# motion_sensor.net
KiCad netlist of a schematic drawn in EAGLE
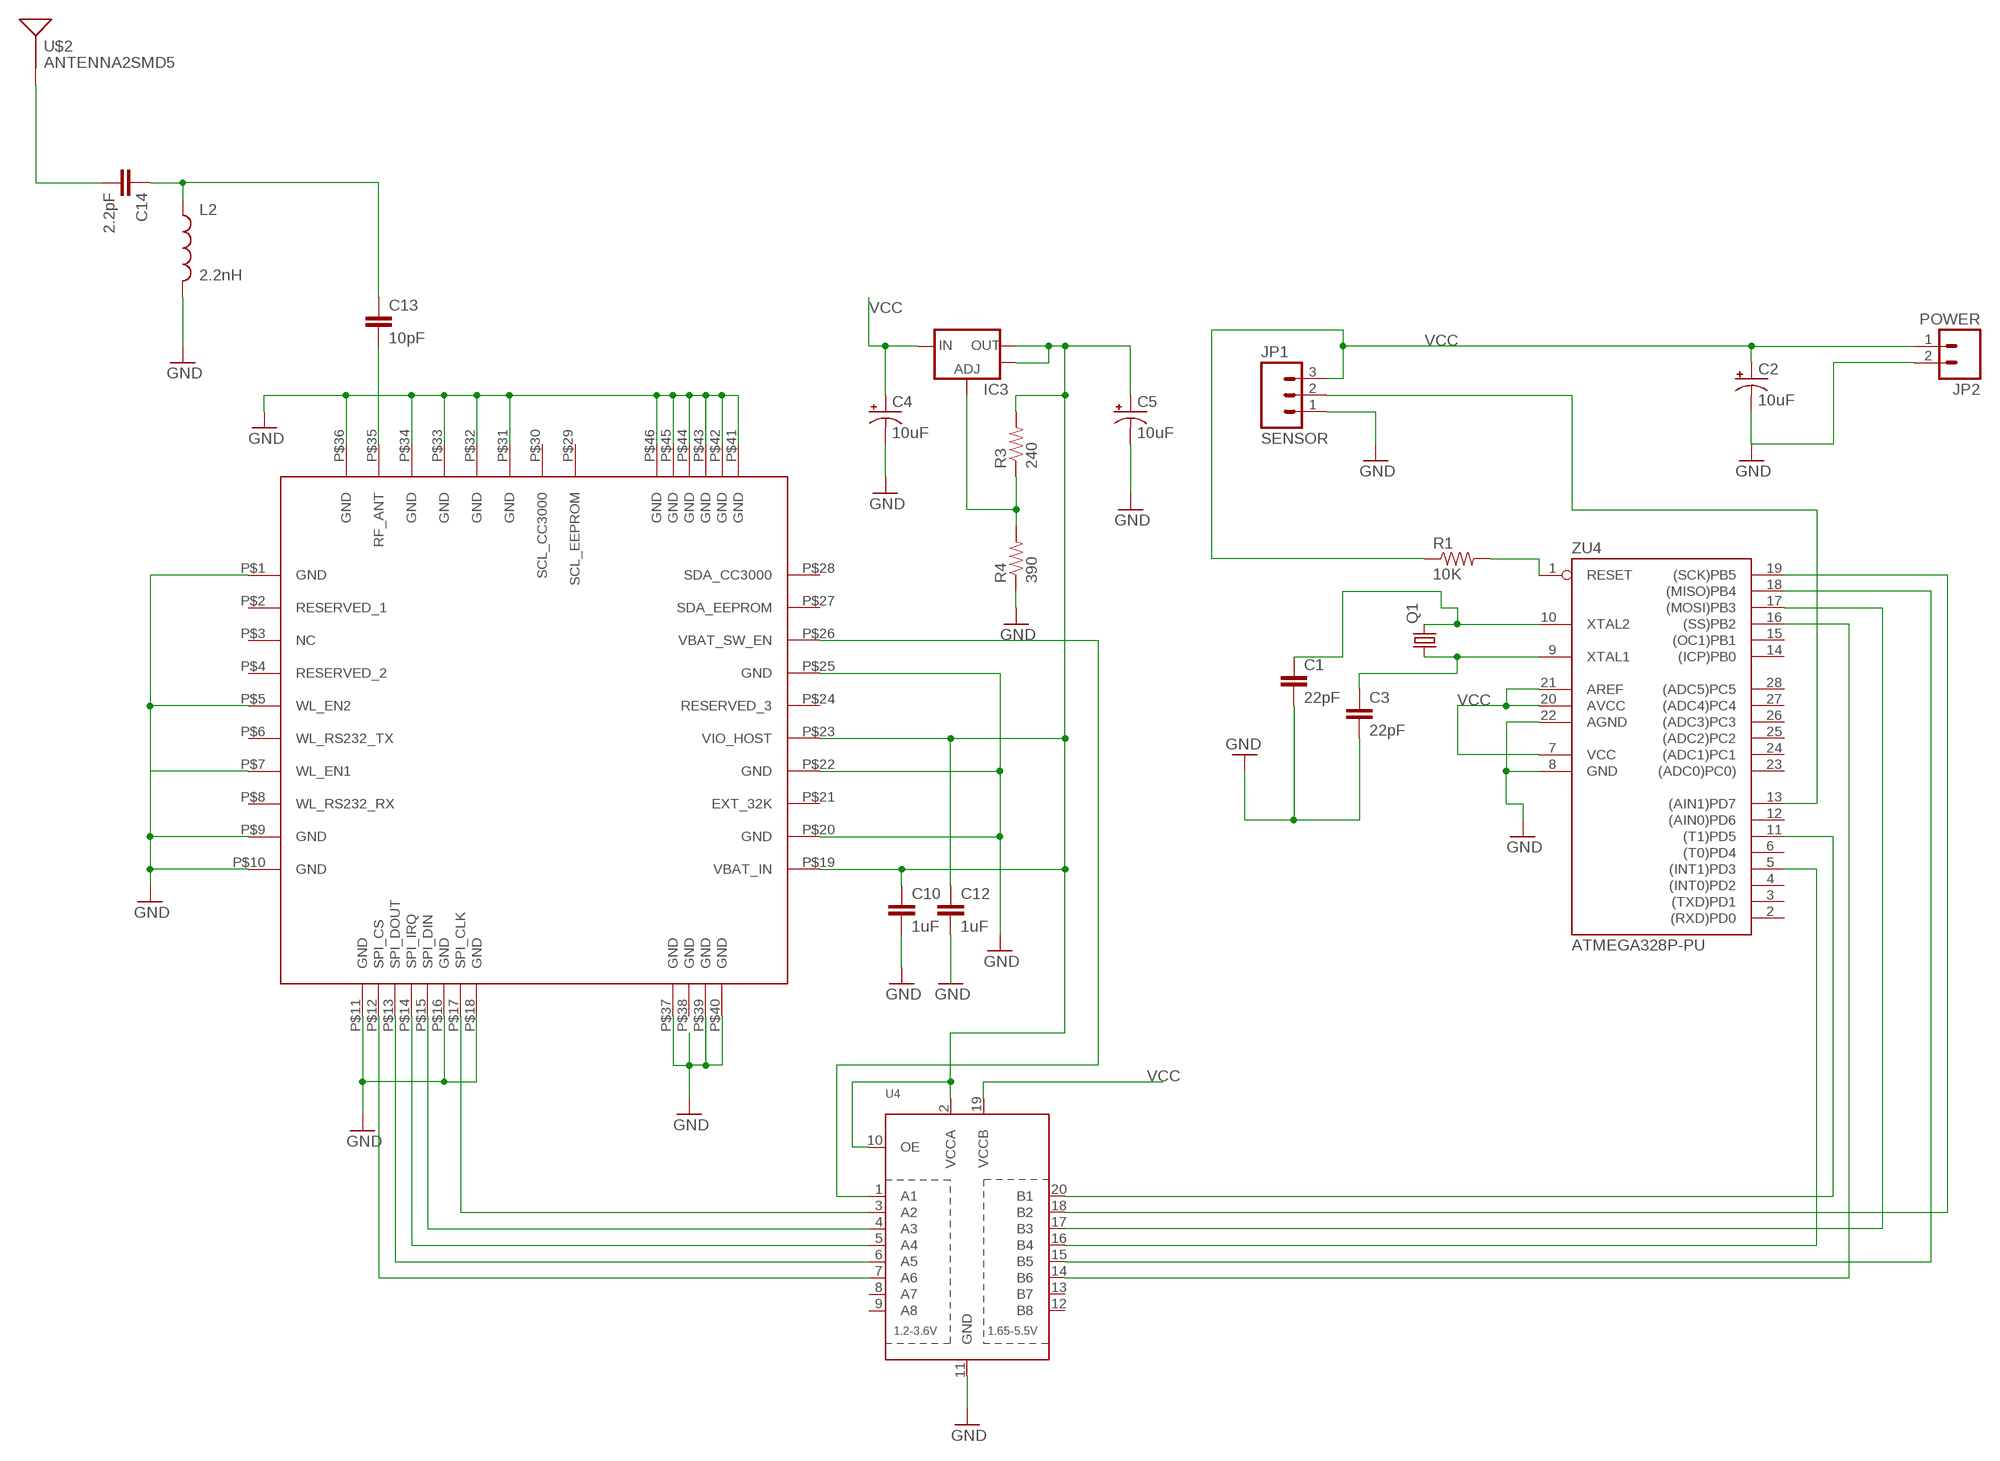
[diagram p0: schematic, sheet 1]

(export (version "E")
  (design (tool "Eeschema 10.0.6"))
  (components
    (comp (ref "C1")
      (value "22pF")
      (footprint "eagle-import:0805")
      (libsource (lib "eagle-import") (part "SparkFun-Passives_CAP0805"))
    )
    (comp (ref "C2")
      (value "10uF")
      (footprint "eagle-import:EIA3216")
      (libsource (lib "eagle-import") (part "CAP_POL1206"))
    )
    (comp (ref "C3")
      (value "22pF")
      (footprint "eagle-import:0805")
      (libsource (lib "eagle-import") (part "SparkFun-Passives_CAP0805"))
    )
    (comp (ref "C4")
      (value "10uF")
      (footprint "eagle-import:EIA3528")
      (libsource (lib "eagle-import") (part "CAP_POL3528"))
    )
    (comp (ref "C5")
      (value "10uF")
      (footprint "eagle-import:EIA3528")
      (libsource (lib "eagle-import") (part "CAP_POL3528"))
    )
    (comp (ref "C10")
      (value "1uF")
      (footprint "eagle-import:1206")
      (libsource (lib "eagle-import") (part "CAP1206"))
    )
    (comp (ref "C12")
      (value "1uF")
      (footprint "eagle-import:1206")
      (libsource (lib "eagle-import") (part "CAP1206"))
    )
    (comp (ref "C13")
      (value "10pF")
      (footprint "eagle-import:0805")
      (libsource (lib "eagle-import") (part "CAP0805"))
    )
    (comp (ref "C14")
      (value "2.2pF")
      (footprint "eagle-import:0805")
      (libsource (lib "eagle-import") (part "CAP0805"))
    )
    (comp (ref "IC3")
      (value "V_REG_LM1117SOT223")
      (footprint "eagle-import:SOT223")
      (libsource (lib "eagle-import") (part "V_REG_LM1117SOT223"))
    )
    (comp (ref "JP1")
      (value "SENSOR")
      (footprint "eagle-import:1X03")
      (libsource (lib "eagle-import") (part "M03PTH"))
    )
    (comp (ref "JP2")
      (value "POWER")
      (footprint "eagle-import:1X02")
      (libsource (lib "eagle-import") (part "M02PTH"))
    )
    (comp (ref "L2")
      (value "2.2nH")
      (footprint "eagle-import:0805")
      (libsource (lib "eagle-import") (part "INDUCTOR0805"))
    )
    (comp (ref "Q1")
      (value "CRYSTALHC49U-V")
      (footprint "eagle-import:HC49U-V")
      (libsource (lib "eagle-import") (part "CRYSTALHC49U-V"))
    )
    (comp (ref "R1")
      (value "10K")
      (footprint "eagle-import:0805")
      (libsource (lib "eagle-import") (part "RESISTOR0805-RES"))
    )
    (comp (ref "R3")
      (value "240")
      (footprint "eagle-import:0805")
      (libsource (lib "eagle-import") (part "SparkFun-Resistors_RESISTOR0805-RES"))
    )
    (comp (ref "R4")
      (value "390")
      (footprint "eagle-import:0805")
      (libsource (lib "eagle-import") (part "SparkFun-Resistors_RESISTOR0805-RES"))
    )
    (comp (ref "U$1")
      (value "CC3000")
      (footprint "eagle-import:CC3000")
      (fields (field (name "AUTHOR") "Matt Bigarani"))
      (libsource (lib "eagle-import") (part "CC3000"))
    )
    (comp (ref "U$2")
      (value "ANTENNA2SMD5")
      (footprint "eagle-import:ANTENNA-CHIP5")
      (libsource (lib "eagle-import") (part "ANTENNA2SMD5"))
    )
    (comp (ref "U4")
      (value "TXB0108PWR")
      (footprint "eagle-import:TSSOP20")
      (libsource (lib "eagle-import") (part "TXB0108PWR"))
    )
    (comp (ref "ZU4")
      (value "ATMEGA328P-PU")
      (footprint "eagle-import:DIL28-3")
      (libsource (lib "eagle-import") (part "ATMEGA328P-PU"))
    )
  )
  (nets
    (net (code "1") (name "/SCL_CC3000") (class "Default")
      (node (ref "U$1") (pin "P$30") (pinfunction "SCL_CC3000_P$30") (pintype "power_in"))
    )
    (net (code "2") (name "/SCL_EEPROM") (class "Default")
      (node (ref "U$1") (pin "P$29") (pinfunction "SCL_EEPROM_P$29") (pintype "power_in"))
    )
    (net (code "3") (name "/VCC") (class "Default")
      (node (ref "C2") (pin "A") (pinfunction "+_A") (pintype "passive"))
      (node (ref "C4") (pin "A") (pinfunction "+_A") (pintype "passive"))
      (node (ref "IC3") (pin "3") (pinfunction "IN_3") (pintype "input"))
      (node (ref "JP1") (pin "3") (pinfunction "3_3") (pintype "passive"))
      (node (ref "JP2") (pin "1") (pinfunction "1_1") (pintype "passive"))
      (node (ref "R1") (pin "1") (pinfunction "1_1") (pintype "passive"))
      (node (ref "U4") (pin "19") (pinfunction "VCCB_19") (pintype "bidirectional"))
      (node (ref "ZU4") (pin "20") (pinfunction "AVCC_20") (pintype "power_in"))
      (node (ref "ZU4") (pin "21") (pinfunction "AREF_21") (pintype "passive"))
      (node (ref "ZU4") (pin "7") (pinfunction "VCC_7") (pintype "power_in"))
    )
    (net (code "4") (name "GND") (class "Default")
      (node (ref "C1") (pin "2") (pinfunction "2_2") (pintype "passive"))
      (node (ref "C10") (pin "2") (pinfunction "2_2") (pintype "passive"))
      (node (ref "C2") (pin "C") (pinfunction "-_C") (pintype "passive"))
      (node (ref "C3") (pin "2") (pinfunction "2_2") (pintype "passive"))
      (node (ref "C4") (pin "C") (pinfunction "-_C") (pintype "passive"))
      (node (ref "C5") (pin "C") (pinfunction "-_C") (pintype "passive"))
      (node (ref "JP1") (pin "1") (pinfunction "1_1") (pintype "passive"))
      (node (ref "JP2") (pin "2") (pinfunction "2_2") (pintype "passive"))
      (node (ref "L2") (pin "2") (pinfunction "2_2") (pintype "passive"))
      (node (ref "R4") (pin "1") (pinfunction "1_1") (pintype "passive"))
      (node (ref "U$1") (pin "P$1") (pinfunction "GND_P$1") (pintype "power_in"))
      (node (ref "U$1") (pin "P$10") (pinfunction "GND_P$10") (pintype "power_in"))
      (node (ref "U$1") (pin "P$11") (pinfunction "GND_P$11") (pintype "power_in"))
      (node (ref "U$1") (pin "P$16") (pinfunction "GND_P$16") (pintype "power_in"))
      (node (ref "U$1") (pin "P$18") (pinfunction "GND_P$18") (pintype "power_in"))
      (node (ref "U$1") (pin "P$20") (pinfunction "GND_P$20") (pintype "bidirectional"))
      (node (ref "U$1") (pin "P$22") (pinfunction "GND_P$22") (pintype "bidirectional"))
      (node (ref "U$1") (pin "P$25") (pinfunction "GND_P$25") (pintype "bidirectional"))
      (node (ref "U$1") (pin "P$31") (pinfunction "GND_P$31") (pintype "power_in"))
      (node (ref "U$1") (pin "P$32") (pinfunction "GND_P$32") (pintype "power_in"))
      (node (ref "U$1") (pin "P$33") (pinfunction "GND_P$33") (pintype "power_in"))
      (node (ref "U$1") (pin "P$34") (pinfunction "GND_P$34") (pintype "power_in"))
      (node (ref "U$1") (pin "P$36") (pinfunction "GND_P$36") (pintype "passive"))
      (node (ref "U$1") (pin "P$37") (pinfunction "GND_P$37") (pintype "power_in"))
      (node (ref "U$1") (pin "P$39") (pinfunction "GND_P$39") (pintype "power_in"))
      (node (ref "U$1") (pin "P$40") (pinfunction "GND_P$40") (pintype "power_in"))
      (node (ref "U$1") (pin "P$41") (pinfunction "GND_P$41") (pintype "power_in"))
      (node (ref "U$1") (pin "P$42") (pinfunction "GND_P$42") (pintype "power_in"))
      (node (ref "U$1") (pin "P$43") (pinfunction "GND_P$43") (pintype "power_in"))
      (node (ref "U$1") (pin "P$44") (pinfunction "GND_P$44") (pintype "power_in"))
      (node (ref "U$1") (pin "P$45") (pinfunction "GND_P$45") (pintype "power_in"))
      (node (ref "U$1") (pin "P$46") (pinfunction "GND_P$46") (pintype "power_in"))
      (node (ref "U$1") (pin "P$5") (pinfunction "WL_EN2_P$5") (pintype "bidirectional"))
      (node (ref "U$1") (pin "P$7") (pinfunction "WL_EN1_P$7") (pintype "bidirectional"))
      (node (ref "U$1") (pin "P$9") (pinfunction "GND_P$9") (pintype "bidirectional"))
      (node (ref "U4") (pin "11") (pinfunction "GND_11") (pintype "bidirectional"))
      (node (ref "ZU4") (pin "22") (pinfunction "AGND_22") (pintype "power_in"))
      (node (ref "ZU4") (pin "8") (pinfunction "GND_8") (pintype "power_in"))
    )
    (net (code "5") (name "Net-(C5-+)") (class "Default")
      (node (ref "C10") (pin "1") (pinfunction "1_1") (pintype "passive"))
      (node (ref "C12") (pin "1") (pinfunction "1_1") (pintype "passive"))
      (node (ref "C5") (pin "A") (pinfunction "+_A") (pintype "passive"))
      (node (ref "IC3") (pin "2") (pinfunction "OUT_2") (pintype "output"))
      (node (ref "IC3") (pin "4") (pinfunction "OUT_4") (pintype "output"))
      (node (ref "R3") (pin "2") (pinfunction "2_2") (pintype "passive"))
      (node (ref "U$1") (pin "P$19") (pinfunction "VBAT_IN_P$19") (pintype "bidirectional"))
      (node (ref "U$1") (pin "P$23") (pinfunction "VIO_HOST_P$23") (pintype "bidirectional"))
      (node (ref "U4") (pin "10") (pinfunction "OE_10") (pintype "bidirectional"))
      (node (ref "U4") (pin "2") (pinfunction "VCCA_2") (pintype "bidirectional"))
    )
    (net (code "6") (name "Net-(C13-Pad1)") (class "Default")
      (node (ref "C13") (pin "1") (pinfunction "1_1") (pintype "passive"))
      (node (ref "C14") (pin "1") (pinfunction "1_1") (pintype "passive"))
      (node (ref "L2") (pin "1") (pinfunction "1_1") (pintype "passive"))
    )
    (net (code "7") (name "Net-(IC3-ADJ)") (class "Default")
      (node (ref "IC3") (pin "1") (pinfunction "ADJ_1") (pintype "input"))
      (node (ref "R3") (pin "1") (pinfunction "1_1") (pintype "passive"))
      (node (ref "R4") (pin "2") (pinfunction "2_2") (pintype "passive"))
    )
    (net (code "8") (name "Net-(U$1-RF_ANT)") (class "Default")
      (node (ref "C13") (pin "2") (pinfunction "2_2") (pintype "passive"))
      (node (ref "U$1") (pin "P$35") (pinfunction "RF_ANT_P$35") (pintype "bidirectional"))
    )
    (net (code "9") (name "Net-(U$1-SPI_CLK)") (class "Default")
      (node (ref "U$1") (pin "P$17") (pinfunction "SPI_CLK_P$17") (pintype "bidirectional"))
      (node (ref "U4") (pin "3") (pinfunction "A2_3") (pintype "bidirectional"))
    )
    (net (code "10") (name "Net-(U$1-SPI_CS)") (class "Default")
      (node (ref "U$1") (pin "P$12") (pinfunction "SPI_CS_P$12") (pintype "bidirectional"))
      (node (ref "U4") (pin "7") (pinfunction "A6_7") (pintype "bidirectional"))
    )
    (net (code "11") (name "Net-(U$1-SPI_DIN)") (class "Default")
      (node (ref "U$1") (pin "P$15") (pinfunction "SPI_DIN_P$15") (pintype "bidirectional"))
      (node (ref "U4") (pin "4") (pinfunction "A3_4") (pintype "bidirectional"))
    )
    (net (code "12") (name "Net-(U$1-SPI_DOUT)") (class "Default")
      (node (ref "U$1") (pin "P$13") (pinfunction "SPI_DOUT_P$13") (pintype "bidirectional"))
      (node (ref "U4") (pin "6") (pinfunction "A5_6") (pintype "bidirectional"))
    )
    (net (code "13") (name "Net-(U$1-SPI_IRQ)") (class "Default")
      (node (ref "U$1") (pin "P$14") (pinfunction "SPI_IRQ_P$14") (pintype "bidirectional"))
      (node (ref "U4") (pin "5") (pinfunction "A4_5") (pintype "bidirectional"))
    )
    (net (code "14") (name "Net-(U$1-VBAT_SW_EN)") (class "Default")
      (node (ref "U$1") (pin "P$26") (pinfunction "VBAT_SW_EN_P$26") (pintype "bidirectional"))
      (node (ref "U4") (pin "1") (pinfunction "A1_1") (pintype "bidirectional"))
    )
    (net (code "15") (name "Net-(U$2-SIGNAL)") (class "Default")
      (node (ref "C14") (pin "2") (pinfunction "2_2") (pintype "passive"))
      (node (ref "U$2") (pin "FEED") (pinfunction "SIGNAL_FEED") (pintype "bidirectional"))
    )
    (net (code "16") (name "Net-(U4-B1)") (class "Default")
      (node (ref "U4") (pin "20") (pinfunction "B1_20") (pintype "bidirectional"))
      (node (ref "ZU4") (pin "11") (pinfunction "(T1)PD5_11") (pintype "bidirectional"))
    )
    (net (code "17") (name "Net-(U4-B2)") (class "Default")
      (node (ref "U4") (pin "18") (pinfunction "B2_18") (pintype "bidirectional"))
      (node (ref "ZU4") (pin "19") (pinfunction "(SCK)PB5_19") (pintype "bidirectional"))
    )
    (net (code "18") (name "Net-(U4-B3)") (class "Default")
      (node (ref "U4") (pin "17") (pinfunction "B3_17") (pintype "bidirectional"))
      (node (ref "ZU4") (pin "17") (pinfunction "(MOSI)PB3_17") (pintype "bidirectional"))
    )
    (net (code "19") (name "Net-(U4-B4)") (class "Default")
      (node (ref "U4") (pin "16") (pinfunction "B4_16") (pintype "bidirectional"))
      (node (ref "ZU4") (pin "5") (pinfunction "(INT1)PD3_5") (pintype "bidirectional"))
    )
    (net (code "20") (name "Net-(U4-B5)") (class "Default")
      (node (ref "U4") (pin "15") (pinfunction "B5_15") (pintype "bidirectional"))
      (node (ref "ZU4") (pin "18") (pinfunction "(MISO)PB4_18") (pintype "bidirectional"))
    )
    (net (code "21") (name "Net-(U4-B6)") (class "Default")
      (node (ref "U4") (pin "14") (pinfunction "B6_14") (pintype "bidirectional"))
      (node (ref "ZU4") (pin "16") (pinfunction "(SS)PB2_16") (pintype "bidirectional"))
    )
    (net (code "22") (name "Net-(ZU4-(AIN1)PD7)") (class "Default")
      (node (ref "JP1") (pin "2") (pinfunction "2_2") (pintype "passive"))
      (node (ref "ZU4") (pin "13") (pinfunction "(AIN1)PD7_13") (pintype "bidirectional"))
    )
    (net (code "23") (name "Net-(ZU4-RESET)") (class "Default")
      (node (ref "R1") (pin "2") (pinfunction "2_2") (pintype "passive"))
      (node (ref "ZU4") (pin "1") (pinfunction "RESET_1") (pintype "input"))
    )
    (net (code "24") (name "Net-(ZU4-XTAL1)") (class "Default")
      (node (ref "C3") (pin "1") (pinfunction "1_1") (pintype "passive"))
      (node (ref "Q1") (pin "1") (pinfunction "1_1") (pintype "passive"))
      (node (ref "ZU4") (pin "9") (pinfunction "XTAL1_9") (pintype "bidirectional"))
    )
    (net (code "25") (name "Net-(ZU4-XTAL2)") (class "Default")
      (node (ref "C1") (pin "1") (pinfunction "1_1") (pintype "passive"))
      (node (ref "Q1") (pin "2") (pinfunction "2_2") (pintype "passive"))
      (node (ref "ZU4") (pin "10") (pinfunction "XTAL2_10") (pintype "bidirectional"))
    )
    (net (code "26") (name "unconnected-(C12-Pad2)") (class "Default")
      (node (ref "C12") (pin "2") (pinfunction "2_2") (pintype "passive"))
    )
    (net (code "27") (name "unconnected-(U$1-EXT_32K-PadP$21)") (class "Default")
      (node (ref "U$1") (pin "P$21") (pinfunction "EXT_32K_P$21") (pintype "bidirectional"))
    )
    (net (code "28") (name "unconnected-(U$1-GND-PadP$38)") (class "Default")
      (node (ref "U$1") (pin "P$38") (pinfunction "GND_P$38") (pintype "passive"))
    )
    (net (code "29") (name "unconnected-(U$1-NC-PadP$3)") (class "Default")
      (node (ref "U$1") (pin "P$3") (pinfunction "NC_P$3") (pintype "no_connect"))
    )
    (net (code "30") (name "unconnected-(U$1-RESERVED_1-PadP$2)") (class "Default")
      (node (ref "U$1") (pin "P$2") (pinfunction "RESERVED_1_P$2") (pintype "bidirectional"))
    )
    (net (code "31") (name "unconnected-(U$1-RESERVED_2-PadP$4)") (class "Default")
      (node (ref "U$1") (pin "P$4") (pinfunction "RESERVED_2_P$4") (pintype "bidirectional"))
    )
    (net (code "32") (name "unconnected-(U$1-RESERVED_3-PadP$24)") (class "Default")
      (node (ref "U$1") (pin "P$24") (pinfunction "RESERVED_3_P$24") (pintype "bidirectional"))
    )
    (net (code "33") (name "unconnected-(U$1-SDA_CC3000-PadP$28)") (class "Default")
      (node (ref "U$1") (pin "P$28") (pinfunction "SDA_CC3000_P$28") (pintype "bidirectional"))
    )
    (net (code "34") (name "unconnected-(U$1-SDA_EEPROM-PadP$27)") (class "Default")
      (node (ref "U$1") (pin "P$27") (pinfunction "SDA_EEPROM_P$27") (pintype "bidirectional"))
    )
    (net (code "35") (name "unconnected-(U$1-WL_RS232_RX-PadP$8)") (class "Default")
      (node (ref "U$1") (pin "P$8") (pinfunction "WL_RS232_RX_P$8") (pintype "bidirectional"))
    )
    (net (code "36") (name "unconnected-(U$1-WL_RS232_TX-PadP$6)") (class "Default")
      (node (ref "U$1") (pin "P$6") (pinfunction "WL_RS232_TX_P$6") (pintype "bidirectional"))
    )
    (net (code "37") (name "unconnected-(U4-A7-Pad8)") (class "Default")
      (node (ref "U4") (pin "8") (pinfunction "A7_8") (pintype "bidirectional"))
    )
    (net (code "38") (name "unconnected-(U4-A8-Pad9)") (class "Default")
      (node (ref "U4") (pin "9") (pinfunction "A8_9") (pintype "bidirectional"))
    )
    (net (code "39") (name "unconnected-(U4-B7-Pad13)") (class "Default")
      (node (ref "U4") (pin "13") (pinfunction "B7_13") (pintype "bidirectional"))
    )
    (net (code "40") (name "unconnected-(U4-B8-Pad12)") (class "Default")
      (node (ref "U4") (pin "12") (pinfunction "B8_12") (pintype "bidirectional"))
    )
    (net (code "41") (name "unconnected-(ZU4-(ADC0)PC0)-Pad23)") (class "Default")
      (node (ref "ZU4") (pin "23") (pinfunction "(ADC0)PC0)_23") (pintype "bidirectional"))
    )
    (net (code "42") (name "unconnected-(ZU4-(ADC1)PC1-Pad24)") (class "Default")
      (node (ref "ZU4") (pin "24") (pinfunction "(ADC1)PC1_24") (pintype "bidirectional"))
    )
    (net (code "43") (name "unconnected-(ZU4-(ADC2)PC2-Pad25)") (class "Default")
      (node (ref "ZU4") (pin "25") (pinfunction "(ADC2)PC2_25") (pintype "bidirectional"))
    )
    (net (code "44") (name "unconnected-(ZU4-(ADC3)PC3-Pad26)") (class "Default")
      (node (ref "ZU4") (pin "26") (pinfunction "(ADC3)PC3_26") (pintype "bidirectional"))
    )
    (net (code "45") (name "unconnected-(ZU4-(ADC4)PC4-Pad27)") (class "Default")
      (node (ref "ZU4") (pin "27") (pinfunction "(ADC4)PC4_27") (pintype "bidirectional"))
    )
    (net (code "46") (name "unconnected-(ZU4-(ADC5)PC5-Pad28)") (class "Default")
      (node (ref "ZU4") (pin "28") (pinfunction "(ADC5)PC5_28") (pintype "bidirectional"))
    )
    (net (code "47") (name "unconnected-(ZU4-(AIN0)PD6-Pad12)") (class "Default")
      (node (ref "ZU4") (pin "12") (pinfunction "(AIN0)PD6_12") (pintype "bidirectional"))
    )
    (net (code "48") (name "unconnected-(ZU4-(ICP)PB0-Pad14)") (class "Default")
      (node (ref "ZU4") (pin "14") (pinfunction "(ICP)PB0_14") (pintype "bidirectional"))
    )
    (net (code "49") (name "unconnected-(ZU4-(INT0)PD2-Pad4)") (class "Default")
      (node (ref "ZU4") (pin "4") (pinfunction "(INT0)PD2_4") (pintype "bidirectional"))
    )
    (net (code "50") (name "unconnected-(ZU4-(OC1)PB1-Pad15)") (class "Default")
      (node (ref "ZU4") (pin "15") (pinfunction "(OC1)PB1_15") (pintype "bidirectional"))
    )
    (net (code "51") (name "unconnected-(ZU4-(RXD)PD0-Pad2)") (class "Default")
      (node (ref "ZU4") (pin "2") (pinfunction "(RXD)PD0_2") (pintype "bidirectional"))
    )
    (net (code "52") (name "unconnected-(ZU4-(T0)PD4-Pad6)") (class "Default")
      (node (ref "ZU4") (pin "6") (pinfunction "(T0)PD4_6") (pintype "bidirectional"))
    )
    (net (code "53") (name "unconnected-(ZU4-(TXD)PD1-Pad3)") (class "Default")
      (node (ref "ZU4") (pin "3") (pinfunction "(TXD)PD1_3") (pintype "bidirectional"))
    )
  )
)
